# AQCA-Light-Control-Blue-A0.net
KiCad netlist of a schematic drawn in Altium Designer
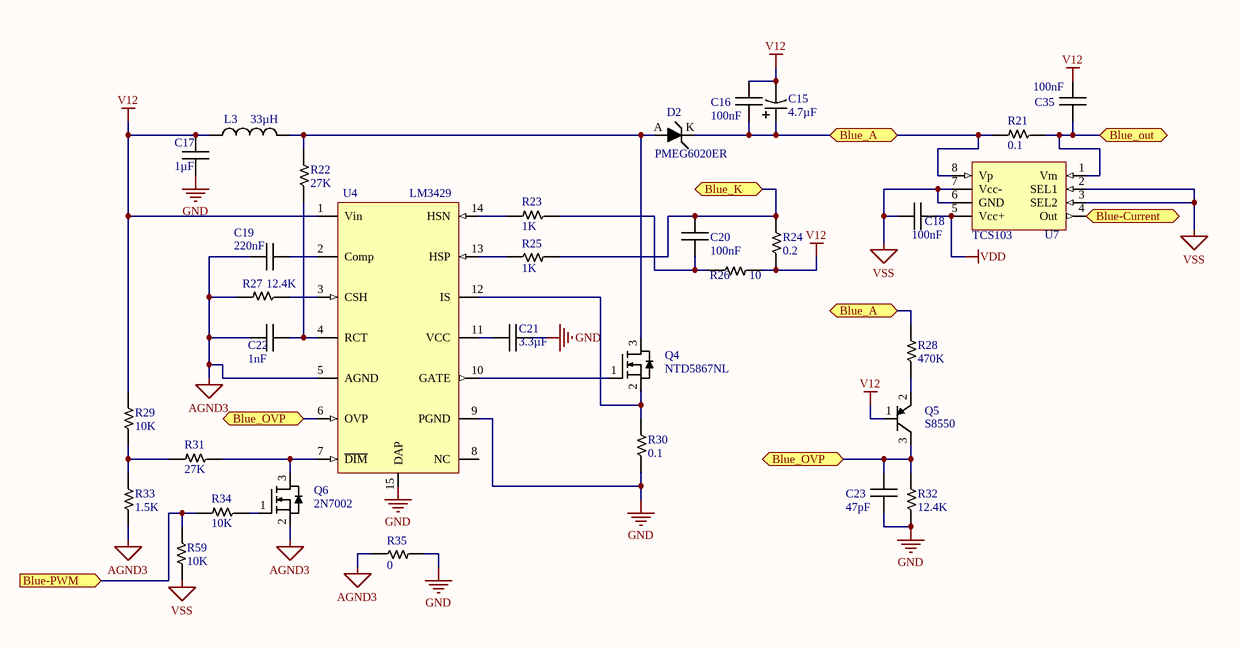
[diagram p0: AQCA-Light-Control-Blue-A0.SchDoc]

(export (version "E")
  (design (tool "Eeschema 10.0.6"))
  (components
    (comp (ref "C15")
      (value "4.7µF")
      (footprint "CAPPR2-5x11")
      (fields (field (name "VOLTAGE") "100V"))
      (libsource (lib "Megaxone") (part "Capacitor Polarised"))
    )
    (comp (ref "C16")
      (value "100nF")
      (footprint "CAPC2012N")
      (fields (field (name "VOLTAGE") "100V"))
      (libsource (lib "Megaxone") (part "Capacitor"))
    )
    (comp (ref "C17")
      (value "1µF")
      (footprint "CAPC1608N")
      (fields (field (name "VOLTAGE") "25V"))
      (libsource (lib "Megaxone") (part "Capacitor"))
    )
    (comp (ref "C18")
      (value "100nF")
      (footprint "CAPC1608N")
      (fields (field (name "VOLTAGE") "16V"))
      (libsource (lib "Megaxone") (part "Capacitor"))
    )
    (comp (ref "C19")
      (value "220nF")
      (footprint "CAPC1608N")
      (fields (field (name "VOLTAGE") "25V"))
      (libsource (lib "Megaxone") (part "Capacitor"))
    )
    (comp (ref "C20")
      (value "100nF")
      (footprint "CAPC1608N")
      (fields (field (name "VOLTAGE") "50V"))
      (libsource (lib "Megaxone") (part "Capacitor"))
    )
    (comp (ref "C21")
      (value "3.3µF")
      (footprint "CAPC1608N")
      (fields (field (name "VOLTAGE") "16V"))
      (libsource (lib "Megaxone") (part "Capacitor"))
    )
    (comp (ref "C22")
      (value "1nF")
      (footprint "CAPC1608N")
      (fields (field (name "VOLTAGE") "50V"))
      (libsource (lib "Megaxone") (part "Capacitor"))
    )
    (comp (ref "C23")
      (value "47pF")
      (footprint "CAPC1608N")
      (fields (field (name "VOLTAGE") "100V"))
      (libsource (lib "Megaxone") (part "Capacitor"))
    )
    (comp (ref "C35")
      (value "100nF")
      (footprint "CAPC2012N")
      (fields (field (name "VOLTAGE") "100V"))
      (libsource (lib "Megaxone") (part "Capacitor"))
    )
    (comp (ref "D2")
      (value "PMEG6020ER")
      (footprint "SOD123")
      (libsource (lib "Megaxone") (part "Schottky Diode"))
    )
    (comp (ref "L3")
      (value "33µH")
      (footprint "Inductor AIUR5-6")
      (libsource (lib "Megaxone") (part "Inductor"))
    )
    (comp (ref "Q4")
      (value "NTD5867NL")
      (footprint "DPAK 369AA")
      (libsource (lib "Megaxone") (part "MOSFET N-Ch"))
    )
    (comp (ref "Q5") (value "S8550") (footprint "SOT23_N") (libsource (lib "Megaxone") (part "PNP")))
    (comp (ref "Q6")
      (value "2N7002")
      (footprint "SOT23-3N")
      (libsource (lib "Megaxone") (part "MOSFET N-Ch"))
    )
    (comp (ref "R21") (value "0.1") (footprint "RESC2012N") (libsource (lib "") (part "Resistor_1")))
    (comp (ref "R22") (value "27K") (footprint "RESC1608N") (libsource (lib "Megaxone") (part "Resistor")))
    (comp (ref "R23") (value "1K") (footprint "RESC1608N") (libsource (lib "") (part "Resistor_1")))
    (comp (ref "R24") (value "0.2") (footprint "RESC6332N") (libsource (lib "Megaxone") (part "Resistor")))
    (comp (ref "R25") (value "1K") (footprint "RESC1608N") (libsource (lib "") (part "Resistor_2")))
    (comp (ref "R26") (value "10") (footprint "RESC1608N") (libsource (lib "") (part "Resistor_2")))
    (comp (ref "R27") (value "12.4K") (footprint "RESC1608N") (libsource (lib "") (part "Resistor_1")))
    (comp (ref "R28") (value "470K") (footprint "RESC1608N") (libsource (lib "Megaxone") (part "Resistor")))
    (comp (ref "R29") (value "10K") (footprint "RESC1608N") (libsource (lib "Megaxone") (part "Resistor")))
    (comp (ref "R30") (value "0.1") (footprint "RESC6332N") (libsource (lib "Megaxone") (part "Resistor")))
    (comp (ref "R31") (value "27K") (footprint "RESC1608N") (libsource (lib "") (part "Resistor_1")))
    (comp (ref "R32") (value "12.4K") (footprint "RESC1608N") (libsource (lib "Megaxone") (part "Resistor")))
    (comp (ref "R33") (value "1.5K") (footprint "RESC1608N") (libsource (lib "Megaxone") (part "Resistor")))
    (comp (ref "R34") (value "10K") (footprint "RESC1608N") (libsource (lib "") (part "Resistor_1")))
    (comp (ref "R35") (value "0") (footprint "RESC1608N") (libsource (lib "") (part "Resistor_2")))
    (comp (ref "R59") (value "10K") (footprint "RESC1608N") (libsource (lib "") (part "Resistor_3")))
    (comp (ref "U4")
      (value "LM3429")
      (footprint "TSOP65P640_HS-14N")
      (libsource (lib "Megaxone") (part "LM3429"))
    )
    (comp (ref "U7") (value "TCS103") (footprint "TSSOP8N_N") (libsource (lib "Megaxone") (part "TCS103")))
  )
  (nets
    (net (code "1") (name "/Blue-Current") (class "Default")
      (node (ref "U7") (pin "4") (pinfunction "Out_4") (pintype "output"))
    )
    (net (code "2") (name "/Blue-PWM") (class "Default")
      (node (ref "R34") (pin "2") (pinfunction "2_2") (pintype "passive"))
      (node (ref "R59") (pin "1") (pinfunction "1_1") (pintype "passive"))
    )
    (net (code "3") (name "/Blue_A") (class "Default")
      (node (ref "C15") (pin "1") (pinfunction "1_1") (pintype "passive"))
      (node (ref "C16") (pin "1") (pinfunction "1_1") (pintype "passive"))
      (node (ref "D2") (pin "K") (pinfunction "Kathode_K") (pintype "power_in"))
      (node (ref "R21") (pin "2") (pinfunction "2_2") (pintype "passive"))
      (node (ref "R28") (pin "2") (pinfunction "2_2") (pintype "passive"))
      (node (ref "U7") (pin "8") (pinfunction "Vp_8") (pintype "input"))
    )
    (net (code "4") (name "/Blue_K") (class "Default")
      (node (ref "C20") (pin "2") (pinfunction "2_2") (pintype "passive"))
      (node (ref "R24") (pin "2") (pinfunction "2_2") (pintype "passive"))
      (node (ref "R25") (pin "2") (pinfunction "2_2") (pintype "passive"))
    )
    (net (code "5") (name "/Blue_OVP") (class "Default")
      (node (ref "C23") (pin "2") (pinfunction "2_2") (pintype "passive"))
      (node (ref "Q5") (pin "3") (pinfunction "C_3") (pintype "passive"))
      (node (ref "R32") (pin "2") (pinfunction "2_2") (pintype "passive"))
      (node (ref "U4") (pin "6") (pinfunction "OVP_6") (pintype "input"))
    )
    (net (code "6") (name "/Blue_out") (class "Default")
      (node (ref "C35") (pin "1") (pinfunction "1_1") (pintype "passive"))
      (node (ref "R21") (pin "1") (pinfunction "1_1") (pintype "passive"))
      (node (ref "U7") (pin "1") (pinfunction "Vm_1") (pintype "input"))
    )
    (net (code "7") (name "AGND3") (class "Default")
      (node (ref "C19") (pin "1") (pinfunction "1_1") (pintype "passive"))
      (node (ref "C22") (pin "1") (pinfunction "1_1") (pintype "passive"))
      (node (ref "Q6") (pin "2") (pinfunction "S_2") (pintype "passive"))
      (node (ref "R27") (pin "2") (pinfunction "2_2") (pintype "passive"))
      (node (ref "R33") (pin "1") (pinfunction "1_1") (pintype "passive"))
      (node (ref "R35") (pin "1") (pinfunction "1_1") (pintype "passive"))
      (node (ref "U4") (pin "5") (pinfunction "AGND_5") (pintype "power_in"))
    )
    (net (code "8") (name "GND") (class "Default")
      (node (ref "C17") (pin "1") (pinfunction "1_1") (pintype "passive"))
      (node (ref "C21") (pin "1") (pinfunction "1_1") (pintype "passive"))
      (node (ref "C23") (pin "1") (pinfunction "1_1") (pintype "passive"))
      (node (ref "R30") (pin "1") (pinfunction "1_1") (pintype "passive"))
      (node (ref "R32") (pin "1") (pinfunction "1_1") (pintype "passive"))
      (node (ref "R35") (pin "2") (pinfunction "2_2") (pintype "passive"))
      (node (ref "U4") (pin "15") (pinfunction "DAP_15") (pintype "passive"))
      (node (ref "U4") (pin "9") (pinfunction "PGND_9") (pintype "power_in"))
    )
    (net (code "9") (name "Net-(C20-Pad1)") (class "Default")
      (node (ref "C20") (pin "1") (pinfunction "1_1") (pintype "passive"))
      (node (ref "R23") (pin "1") (pinfunction "1_1") (pintype "passive"))
      (node (ref "R26") (pin "1") (pinfunction "1_1") (pintype "passive"))
    )
    (net (code "10") (name "Net-(D2-Anode)") (class "Default")
      (node (ref "D2") (pin "A") (pinfunction "Anode_A") (pintype "power_in"))
      (node (ref "L3") (pin "2") (pinfunction "2_2") (pintype "passive"))
      (node (ref "Q4") (pin "3") (pinfunction "D_3") (pintype "passive"))
      (node (ref "R22") (pin "2") (pinfunction "2_2") (pintype "passive"))
    )
    (net (code "11") (name "Net-(Q4-G)") (class "Default")
      (node (ref "Q4") (pin "1") (pinfunction "G_1") (pintype "passive"))
      (node (ref "U4") (pin "10") (pinfunction "GATE_10") (pintype "output"))
    )
    (net (code "12") (name "Net-(Q4-S)") (class "Default")
      (node (ref "Q4") (pin "2") (pinfunction "S_2") (pintype "passive"))
      (node (ref "R30") (pin "2") (pinfunction "2_2") (pintype "passive"))
      (node (ref "U4") (pin "12") (pinfunction "IS_12") (pintype "passive"))
    )
    (net (code "13") (name "Net-(Q5-E)") (class "Default")
      (node (ref "Q5") (pin "2") (pinfunction "E_2") (pintype "passive"))
      (node (ref "R28") (pin "1") (pinfunction "1_1") (pintype "passive"))
    )
    (net (code "14") (name "Net-(Q6-D)") (class "Default")
      (node (ref "Q6") (pin "3") (pinfunction "D_3") (pintype "passive"))
      (node (ref "R31") (pin "1") (pinfunction "1_1") (pintype "passive"))
      (node (ref "U4") (pin "7") (pinfunction "~{DIM}_7") (pintype "input"))
    )
    (net (code "15") (name "Net-(Q6-G)") (class "Default")
      (node (ref "Q6") (pin "1") (pinfunction "G_1") (pintype "passive"))
      (node (ref "R34") (pin "1") (pinfunction "1_1") (pintype "passive"))
    )
    (net (code "16") (name "Net-(R29-Pad1)") (class "Default")
      (node (ref "R29") (pin "1") (pinfunction "1_1") (pintype "passive"))
      (node (ref "R31") (pin "2") (pinfunction "2_2") (pintype "passive"))
      (node (ref "R33") (pin "2") (pinfunction "2_2") (pintype "passive"))
    )
    (net (code "17") (name "Net-(U4-CSH)") (class "Default")
      (node (ref "R27") (pin "1") (pinfunction "1_1") (pintype "passive"))
      (node (ref "U4") (pin "3") (pinfunction "CSH_3") (pintype "input"))
    )
    (net (code "18") (name "Net-(U4-Comp)") (class "Default")
      (node (ref "C19") (pin "2") (pinfunction "2_2") (pintype "passive"))
      (node (ref "U4") (pin "2") (pinfunction "Comp_2") (pintype "passive"))
    )
    (net (code "19") (name "Net-(U4-HSN)") (class "Default")
      (node (ref "R23") (pin "2") (pinfunction "2_2") (pintype "passive"))
      (node (ref "U4") (pin "14") (pinfunction "HSN_14") (pintype "input"))
    )
    (net (code "20") (name "Net-(U4-HSP)") (class "Default")
      (node (ref "R25") (pin "1") (pinfunction "1_1") (pintype "passive"))
      (node (ref "U4") (pin "13") (pinfunction "HSP_13") (pintype "input"))
    )
    (net (code "21") (name "Net-(U4-RCT)") (class "Default")
      (node (ref "C22") (pin "2") (pinfunction "2_2") (pintype "passive"))
      (node (ref "R22") (pin "1") (pinfunction "1_1") (pintype "passive"))
      (node (ref "U4") (pin "4") (pinfunction "RCT_4") (pintype "passive"))
    )
    (net (code "22") (name "Net-(U4-VCC)") (class "Default")
      (node (ref "C21") (pin "2") (pinfunction "2_2") (pintype "passive"))
      (node (ref "U4") (pin "11") (pinfunction "VCC_11") (pintype "power_in"))
    )
    (net (code "23") (name "V12") (class "Default")
      (node (ref "C15") (pin "2") (pinfunction "2_2") (pintype "passive"))
      (node (ref "C16") (pin "2") (pinfunction "2_2") (pintype "passive"))
      (node (ref "C17") (pin "2") (pinfunction "2_2") (pintype "passive"))
      (node (ref "C35") (pin "2") (pinfunction "2_2") (pintype "passive"))
      (node (ref "L3") (pin "1") (pinfunction "1_1") (pintype "passive"))
      (node (ref "Q5") (pin "1") (pinfunction "B_1") (pintype "passive"))
      (node (ref "R24") (pin "1") (pinfunction "1_1") (pintype "passive"))
      (node (ref "R26") (pin "2") (pinfunction "2_2") (pintype "passive"))
      (node (ref "R29") (pin "2") (pinfunction "2_2") (pintype "passive"))
      (node (ref "U4") (pin "1") (pinfunction "Vin_1") (pintype "power_in"))
    )
    (net (code "24") (name "VDD") (class "Default")
      (node (ref "C18") (pin "1") (pinfunction "1_1") (pintype "passive"))
      (node (ref "U7") (pin "5") (pinfunction "Vcc+_5") (pintype "power_in"))
    )
    (net (code "25") (name "VSS") (class "Default")
      (node (ref "C18") (pin "2") (pinfunction "2_2") (pintype "passive"))
      (node (ref "R59") (pin "2") (pinfunction "2_2") (pintype "passive"))
      (node (ref "U7") (pin "2") (pinfunction "SEL1_2") (pintype "input"))
      (node (ref "U7") (pin "3") (pinfunction "SEL2_3") (pintype "input"))
      (node (ref "U7") (pin "6") (pinfunction "GND_6") (pintype "power_in"))
      (node (ref "U7") (pin "7") (pinfunction "Vcc-_7") (pintype "power_in"))
    )
    (net (code "26") (name "unconnected-(U4-NC-Pad8)") (class "Default")
      (node (ref "U4") (pin "8") (pinfunction "NC_8") (pintype "passive"))
    )
  )
)
